# GPS_track2.net
KiCad netlist of a schematic drawn in Altium Designer
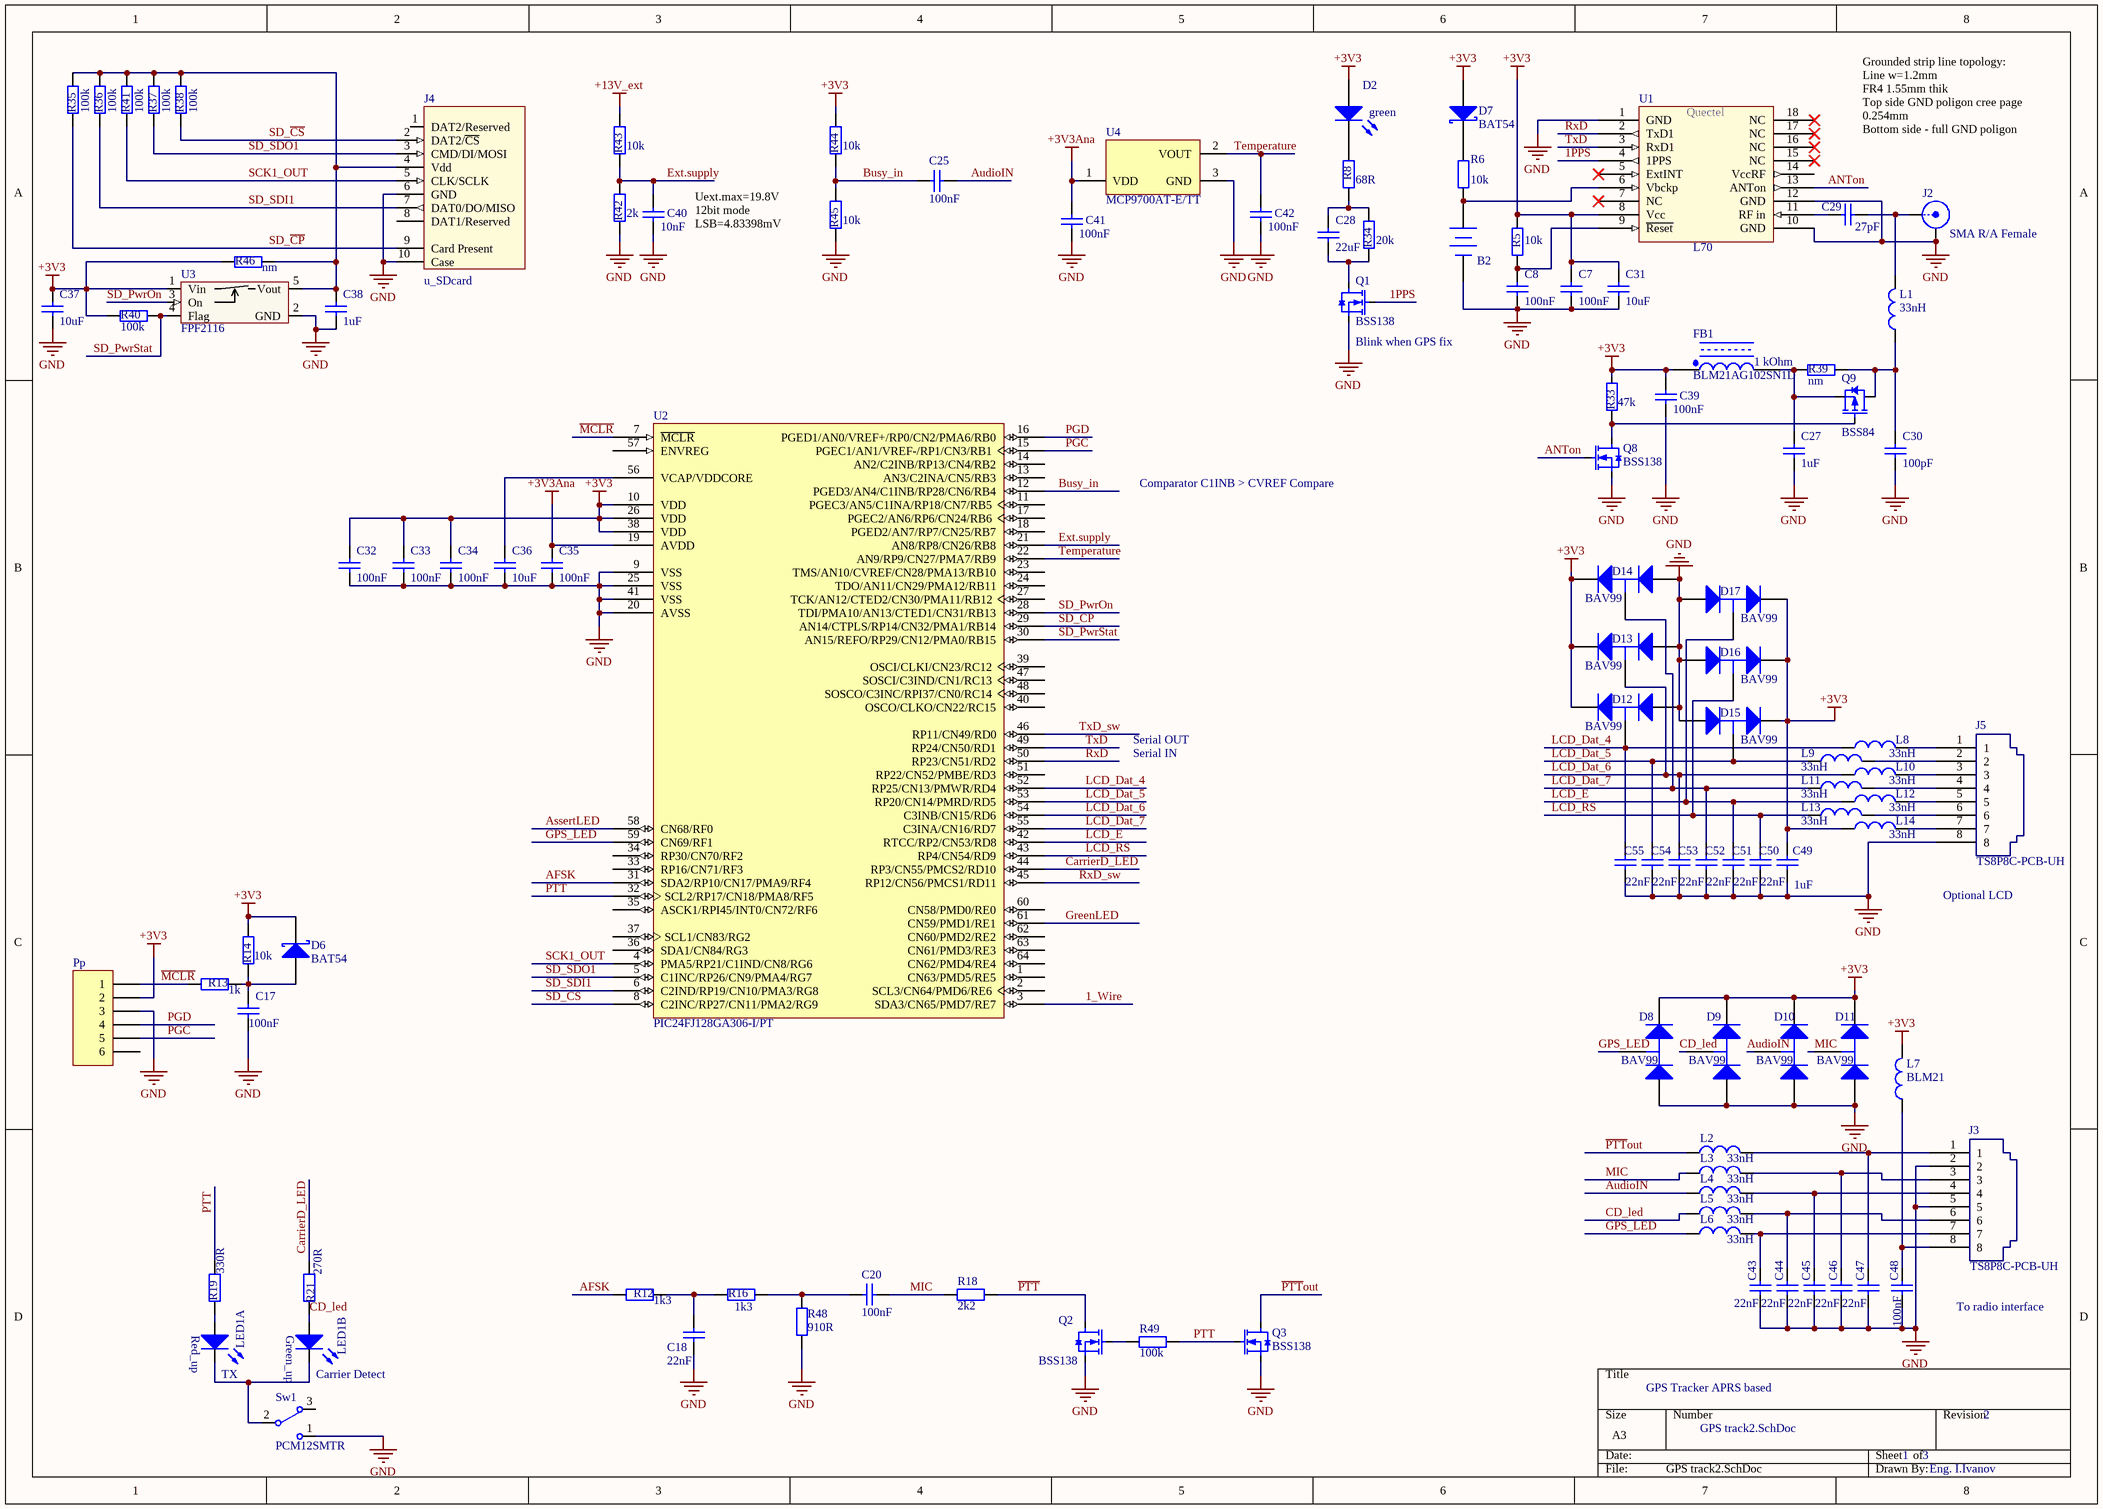
[diagram p0: GPS track2.SchDoc]

(export (version "E")
  (design (tool "Eeschema 10.0.6"))
  (components
    (comp (ref "B2")
      (value "CR2032 holder")
      (footprint "1065 Keystone")
      (fields (field (name "CREATED BY") "Charge"))
      (libsource (lib "ANG_6VA transformers") (part "CR2032_holder"))
    )
    (comp (ref "C7")
      (value "100nF")
      (footprint "2012[0805]")
      (description "Capacitor (Semiconductor SIM Model)")
      (fields (field (name "Comment") "Cap Semi") (field (name "PUBLISHER") "Altium Limited"))
      (libsource (lib "Miscellaneous Devices") (part "Cap Semi"))
    )
    (comp (ref "C8")
      (value "100nF")
      (footprint "2012[0805]")
      (fields (field (name "Comment") "Cap Semi") (field (name "PUBLISHER") "Altium Limited"))
      (libsource (lib "altium-import") (part "root_1__Miscellaneous Devices.IntLib"))
    )
    (comp (ref "C17")
      (value "100nF")
      (footprint "2012[0805]")
      (description "Capacitor (Semiconductor SIM Model)")
      (fields (field (name "Comment") "Cap Semi") (field (name "PUBLISHER") "Altium Limited"))
      (libsource (lib "Miscellaneous Devices") (part "Cap Semi"))
    )
    (comp (ref "C18")
      (value "22nF")
      (footprint "2012[0805]")
      (description "Capacitor (Semiconductor SIM Model)")
      (fields (field (name "Comment") "Cap Semi") (field (name "PUBLISHER") "Altium Limited"))
      (libsource (lib "Miscellaneous Devices") (part "Cap Semi"))
    )
    (comp (ref "C20")
      (value "100nF")
      (footprint "2012[0805]")
      (description "Capacitor (Semiconductor SIM Model)")
      (fields (field (name "Comment") "Cap Semi") (field (name "PUBLISHER") "Altium Limited"))
      (libsource (lib "Miscellaneous Devices") (part "Cap Semi"))
    )
    (comp (ref "C25")
      (value "100nF")
      (footprint "C0805")
      (description "Capacitor (Semiconductor SIM Model)")
      (fields (field (name "Comment") "Cap Semi") (field (name "PUBLISHER") "Altium Limited"))
      (libsource (lib "Miscellaneous Devices") (part "Cap Semi"))
    )
    (comp (ref "C27")
      (value "1uF")
      (footprint "C0805")
      (description "Capacitor (Semiconductor SIM Model)")
      (fields (field (name "Comment") "Cap Semi") (field (name "PUBLISHER") "Altium Limited"))
      (libsource (lib "Miscellaneous Devices") (part "Cap Semi"))
    )
    (comp (ref "C28")
      (value "22uF")
      (footprint "C0805")
      (description "Capacitor (Semiconductor SIM Model)")
      (fields (field (name "Comment") "Cap Semi") (field (name "PUBLISHER") "Altium Limited"))
      (libsource (lib "Miscellaneous Devices") (part "Cap Semi"))
    )
    (comp (ref "C29")
      (value "27pF")
      (footprint "C0805")
      (description "Capacitor (Semiconductor SIM Model)")
      (fields (field (name "Comment") "Cap Semi") (field (name "PUBLISHER") "Altium Limited"))
      (libsource (lib "Miscellaneous Devices") (part "Cap Semi"))
    )
    (comp (ref "C30")
      (value "100pF")
      (footprint "C0805")
      (description "Capacitor (Semiconductor SIM Model)")
      (fields (field (name "Comment") "Cap Semi") (field (name "PUBLISHER") "Altium Limited"))
      (libsource (lib "Miscellaneous Devices") (part "Cap Semi"))
    )
    (comp (ref "C31")
      (value "10uF")
      (footprint "C0805")
      (description "Capacitor (Semiconductor SIM Model)")
      (fields (field (name "Comment") "Cap Semi") (field (name "PUBLISHER") "Altium Limited"))
      (libsource (lib "Miscellaneous Devices") (part "Cap Semi"))
    )
    (comp (ref "C32")
      (value "100nF")
      (footprint "2012[0805]")
      (description "Capacitor (Semiconductor SIM Model)")
      (fields (field (name "Comment") "Cap Semi") (field (name "PUBLISHER") "Altium Limited"))
      (libsource (lib "Miscellaneous Devices") (part "Cap Semi"))
    )
    (comp (ref "C33")
      (value "100nF")
      (footprint "2012[0805]")
      (description "Capacitor (Semiconductor SIM Model)")
      (fields (field (name "Comment") "Cap Semi") (field (name "PUBLISHER") "Altium Limited"))
      (libsource (lib "Miscellaneous Devices") (part "Cap Semi"))
    )
    (comp (ref "C34")
      (value "100nF")
      (footprint "2012[0805]")
      (description "Capacitor (Semiconductor SIM Model)")
      (fields (field (name "Comment") "Cap Semi") (field (name "PUBLISHER") "Altium Limited"))
      (libsource (lib "Miscellaneous Devices") (part "Cap Semi"))
    )
    (comp (ref "C35")
      (value "100nF")
      (footprint "2012[0805]")
      (description "Capacitor (Semiconductor SIM Model)")
      (fields (field (name "PUBLISHER") "Altium Limited"))
      (libsource (lib "Miscellaneous Devices") (part "Cap Semi"))
    )
    (comp (ref "C36")
      (value "10uF")
      (footprint "2012[0805]")
      (description "Capacitor (Semiconductor SIM Model)")
      (fields (field (name "Comment") "Cap Semi") (field (name "PUBLISHER") "Altium Limited"))
      (libsource (lib "Miscellaneous Devices") (part "Cap Semi"))
    )
    (comp (ref "C37")
      (value "10uF")
      (footprint "2012[0805]")
      (description "Capacitor (Semiconductor SIM Model)")
      (fields (field (name "Comment") "Cap Semi") (field (name "PUBLISHER") "Altium Limited"))
      (libsource (lib "Miscellaneous Devices") (part "Cap Semi"))
    )
    (comp (ref "C38")
      (value "1uF")
      (footprint "2012[0805]")
      (description "Capacitor (Semiconductor SIM Model)")
      (fields (field (name "Comment") "Cap Semi") (field (name "PUBLISHER") "Altium Limited"))
      (libsource (lib "Miscellaneous Devices") (part "Cap Semi"))
    )
    (comp (ref "C39")
      (value "100nF")
      (footprint "C0805")
      (description "Capacitor (Semiconductor SIM Model)")
      (fields (field (name "Comment") "Cap Semi") (field (name "PUBLISHER") "Altium Limited"))
      (libsource (lib "Miscellaneous Devices") (part "Cap Semi"))
    )
    (comp (ref "C40")
      (value "10nF")
      (footprint "C0805")
      (description "Capacitor (Semiconductor SIM Model)")
      (fields (field (name "Comment") "Cap Semi") (field (name "PUBLISHER") "Altium Limited"))
      (libsource (lib "Miscellaneous Devices") (part "Cap Semi"))
    )
    (comp (ref "C41")
      (value "100nF")
      (footprint "C0805")
      (description "Capacitor (Semiconductor SIM Model)")
      (fields (field (name "Comment") "Cap Semi") (field (name "PUBLISHER") "Altium Limited"))
      (libsource (lib "Miscellaneous Devices") (part "Cap Semi"))
    )
    (comp (ref "C42")
      (value "100nF")
      (footprint "C0805")
      (description "Capacitor (Semiconductor SIM Model)")
      (fields (field (name "Comment") "Cap Semi") (field (name "PUBLISHER") "Altium Limited"))
      (libsource (lib "Miscellaneous Devices") (part "Cap Semi"))
    )
    (comp (ref "C43")
      (value "22nF")
      (footprint "C0805")
      (description "Capacitor (Semiconductor SIM Model)")
      (fields (field (name "Comment") "Cap Semi") (field (name "PUBLISHER") "Altium Limited"))
      (libsource (lib "Miscellaneous Devices") (part "Cap Semi"))
    )
    (comp (ref "C44")
      (value "22nF")
      (footprint "C0805")
      (description "Capacitor (Semiconductor SIM Model)")
      (fields (field (name "Comment") "Cap Semi") (field (name "PUBLISHER") "Altium Limited"))
      (libsource (lib "Miscellaneous Devices") (part "Cap Semi"))
    )
    (comp (ref "C45")
      (value "22nF")
      (footprint "C0805")
      (description "Capacitor (Semiconductor SIM Model)")
      (fields (field (name "Comment") "Cap Semi") (field (name "PUBLISHER") "Altium Limited"))
      (libsource (lib "Miscellaneous Devices") (part "Cap Semi"))
    )
    (comp (ref "C46")
      (value "22nF")
      (footprint "C0805")
      (description "Capacitor (Semiconductor SIM Model)")
      (fields (field (name "Comment") "Cap Semi") (field (name "PUBLISHER") "Altium Limited"))
      (libsource (lib "Miscellaneous Devices") (part "Cap Semi"))
    )
    (comp (ref "C47")
      (value "22nF")
      (footprint "C0805")
      (description "Capacitor (Semiconductor SIM Model)")
      (fields (field (name "Comment") "Cap Semi") (field (name "PUBLISHER") "Altium Limited"))
      (libsource (lib "Miscellaneous Devices") (part "Cap Semi"))
    )
    (comp (ref "C48")
      (value "100nF")
      (footprint "C0805")
      (description "Capacitor (Semiconductor SIM Model)")
      (fields (field (name "Comment") "Cap Semi") (field (name "PUBLISHER") "Altium Limited"))
      (libsource (lib "Miscellaneous Devices") (part "Cap Semi"))
    )
    (comp (ref "C49")
      (value "1uF")
      (footprint "C0805")
      (description "Capacitor (Semiconductor SIM Model)")
      (fields (field (name "Comment") "Cap Semi") (field (name "PUBLISHER") "Altium Limited"))
      (libsource (lib "Miscellaneous Devices") (part "Cap Semi"))
    )
    (comp (ref "C50")
      (value "22nF")
      (footprint "C0805")
      (description "Capacitor (Semiconductor SIM Model)")
      (fields (field (name "Comment") "Cap Semi") (field (name "PUBLISHER") "Altium Limited"))
      (libsource (lib "Miscellaneous Devices") (part "Cap Semi"))
    )
    (comp (ref "C51")
      (value "22nF")
      (footprint "C0805")
      (description "Capacitor (Semiconductor SIM Model)")
      (fields (field (name "Comment") "Cap Semi") (field (name "PUBLISHER") "Altium Limited"))
      (libsource (lib "Miscellaneous Devices") (part "Cap Semi"))
    )
    (comp (ref "C52")
      (value "22nF")
      (footprint "C0805")
      (description "Capacitor (Semiconductor SIM Model)")
      (fields (field (name "Comment") "Cap Semi") (field (name "PUBLISHER") "Altium Limited"))
      (libsource (lib "Miscellaneous Devices") (part "Cap Semi"))
    )
    (comp (ref "C53")
      (value "22nF")
      (footprint "C0805")
      (description "Capacitor (Semiconductor SIM Model)")
      (fields (field (name "Comment") "Cap Semi") (field (name "PUBLISHER") "Altium Limited"))
      (libsource (lib "Miscellaneous Devices") (part "Cap Semi"))
    )
    (comp (ref "C54")
      (value "22nF")
      (footprint "C0805")
      (description "Capacitor (Semiconductor SIM Model)")
      (fields (field (name "Comment") "Cap Semi") (field (name "PUBLISHER") "Altium Limited"))
      (libsource (lib "Miscellaneous Devices") (part "Cap Semi"))
    )
    (comp (ref "C55")
      (value "22nF")
      (footprint "C0805")
      (description "Capacitor (Semiconductor SIM Model)")
      (fields (field (name "Comment") "Cap Semi") (field (name "PUBLISHER") "Altium Limited"))
      (libsource (lib "Miscellaneous Devices") (part "Cap Semi"))
    )
    (comp (ref "D2")
      (value "OSTG1206C1A")
      (footprint "3.2X1.6X1.1")
      (description "High Performance SMT Chip LED, Green")
      (fields (field (name "PUBLISHER") "Altium Limited"))
      (libsource (lib "Agilent Optoelectronic LED") (part "HSMM-C150"))
    )
    (comp (ref "D6")
      (value "BAT54")
      (footprint "SOT23_N")
      (description "Schottky Barrier Diode")
      (fields (field (name "PUBLISHER") "Altium Limited"))
      (libsource (lib "Philips Discrete Diode - Schottky") (part "BAT54"))
    )
    (comp (ref "D7")
      (value "BAT54")
      (footprint "SOT23_N")
      (description "Schottky Barrier Diode")
      (fields (field (name "PUBLISHER") "Altium Limited"))
      (libsource (lib "Philips Discrete Diode - Schottky") (part "BAT54"))
    )
    (comp (ref "D8")
      (value "BAV99")
      (footprint "SOT-23")
      (description "Silicon Switching Diode Array for High-Speed Switching")
      (fields (field (name "PUBLISHER") "Altium Limited"))
      (libsource (lib "Infineon Discrete Diode") (part "BAV99"))
    )
    (comp (ref "D9")
      (value "BAV99")
      (footprint "SOT-23")
      (description "Silicon Switching Diode Array for High-Speed Switching")
      (fields (field (name "PUBLISHER") "Altium Limited"))
      (libsource (lib "Infineon Discrete Diode") (part "BAV99"))
    )
    (comp (ref "D10")
      (value "BAV99")
      (footprint "SOT-23")
      (description "Silicon Switching Diode Array for High-Speed Switching")
      (fields (field (name "PUBLISHER") "Altium Limited"))
      (libsource (lib "Infineon Discrete Diode") (part "BAV99"))
    )
    (comp (ref "D11")
      (value "BAV99")
      (footprint "SOT-23")
      (description "Silicon Switching Diode Array for High-Speed Switching")
      (fields (field (name "PUBLISHER") "Altium Limited"))
      (libsource (lib "Infineon Discrete Diode") (part "BAV99"))
    )
    (comp (ref "D12")
      (value "BAV99")
      (footprint "SOT-23")
      (description "Silicon Switching Diode Array for High-Speed Switching")
      (fields (field (name "PUBLISHER") "Altium Limited"))
      (libsource (lib "Infineon Discrete Diode") (part "BAV99"))
    )
    (comp (ref "D13")
      (value "BAV99")
      (footprint "SOT-23")
      (description "Silicon Switching Diode Array for High-Speed Switching")
      (fields (field (name "PUBLISHER") "Altium Limited"))
      (libsource (lib "Infineon Discrete Diode") (part "BAV99"))
    )
    (comp (ref "D14")
      (value "BAV99")
      (footprint "SOT-23")
      (description "Silicon Switching Diode Array for High-Speed Switching")
      (fields (field (name "PUBLISHER") "Altium Limited"))
      (libsource (lib "Infineon Discrete Diode") (part "BAV99"))
    )
    (comp (ref "D15")
      (value "BAV99")
      (footprint "SOT-23")
      (description "Silicon Switching Diode Array for High-Speed Switching")
      (fields (field (name "PUBLISHER") "Altium Limited"))
      (libsource (lib "Infineon Discrete Diode") (part "BAV99"))
    )
    (comp (ref "D16")
      (value "BAV99")
      (footprint "SOT-23")
      (description "Silicon Switching Diode Array for High-Speed Switching")
      (fields (field (name "PUBLISHER") "Altium Limited"))
      (libsource (lib "Infineon Discrete Diode") (part "BAV99"))
    )
    (comp (ref "D17")
      (value "BAV99")
      (footprint "SOT-23")
      (description "Silicon Switching Diode Array for High-Speed Switching")
      (fields (field (name "PUBLISHER") "Altium Limited"))
      (libsource (lib "Infineon Discrete Diode") (part "BAV99"))
    )
    (comp (ref "FB1")
      (value "BLM21AG102SN1D")
      (footprint "RESC2012N")
      (description "Isolated Inductor")
      (fields (field (name "ALTIUM_VALUE") "1 kOhm") (field (name "PUBLISHER") "Altium Limited"))
      (libsource (lib "Miscellaneous Devices") (part "Inductor Isolated"))
    )
    (comp (ref "J2")
      (value "SMA R/A Female")
      (footprint "SMA R/A PCB")
      (fields (field (name "Comment") "SMA R/A PCB") (field (name "CREATED BY") "Charge"))
      (libsource (lib "*") (part "SMA R/A PCB"))
    )
    (comp (ref "J3")
      (value "TS8P8C-PCB-UH")
      (footprint "TS8P8C-PCB-UH")
      (description "Cvilux - CJ3188A1100")
      (libsource (lib "ANG_6VA transformers") (part "TS8P8C-PCB-UH"))
    )
    (comp (ref "J4")
      (value "u_SDcard")
      (footprint "112A-TAAR-R02")
      (fields (field (name "MANUFACTURER") "Attend Technology") (field (name "Comment") "microSD Socket"))
      (libsource (lib "ANG_6VA transformers") (part "Micro SD Socket PP T1"))
    )
    (comp (ref "J5")
      (value "TS8P8C-PCB-UH")
      (footprint "TS8P8C-PCB-UH")
      (description "Cvilux - CJ3188A1100")
      (libsource (lib "ANG_6VA transformers") (part "TS8P8C-PCB-UH"))
    )
    (comp (ref "L1")
      (value "33nH")
      (footprint "CCFH0805 C Series")
      (fields (field (name "Comment") "CCFH 0805 series choke"))
      (libsource (lib "ANG_6VA transformers") (part "CCFH0805 coil Coils"))
    )
    (comp (ref "L2")
      (value "33nH")
      (footprint "CCFH0805 C Series")
      (fields (field (name "Comment") "CCFH 0805 series choke"))
      (libsource (lib "ANG_6VA transformers") (part "CCFH0805 coil Coils"))
    )
    (comp (ref "L3")
      (value "33nH")
      (footprint "CCFH0805 C Series")
      (fields (field (name "Comment") "CCFH 0805 series choke"))
      (libsource (lib "ANG_6VA transformers") (part "CCFH0805 coil Coils"))
    )
    (comp (ref "L4")
      (value "33nH")
      (footprint "CCFH0805 C Series")
      (fields (field (name "Comment") "CCFH 0805 series choke"))
      (libsource (lib "ANG_6VA transformers") (part "CCFH0805 coil Coils"))
    )
    (comp (ref "L5")
      (value "33nH")
      (footprint "CCFH0805 C Series")
      (fields (field (name "Comment") "CCFH 0805 series choke"))
      (libsource (lib "ANG_6VA transformers") (part "CCFH0805 coil Coils"))
    )
    (comp (ref "L6")
      (value "33nH")
      (footprint "CCFH0805 C Series")
      (fields (field (name "Comment") "CCFH 0805 series choke"))
      (libsource (lib "ANG_6VA transformers") (part "CCFH0805 coil Coils"))
    )
    (comp (ref "L7")
      (value "BLM21")
      (footprint "CCFH0805 C Series")
      (fields (field (name "Comment") "CCFH 0805 series choke"))
      (libsource (lib "ANG_6VA transformers") (part "CCFH0805 coil Coils"))
    )
    (comp (ref "L8")
      (value "33nH")
      (footprint "CCFH0805 C Series")
      (fields (field (name "Comment") "CCFH 0805 series choke"))
      (libsource (lib "ANG_6VA transformers") (part "CCFH0805 coil Coils"))
    )
    (comp (ref "L9")
      (value "33nH")
      (footprint "CCFH0805 C Series")
      (fields (field (name "Comment") "CCFH 0805 series choke"))
      (libsource (lib "ANG_6VA transformers") (part "CCFH0805 coil Coils"))
    )
    (comp (ref "L10")
      (value "33nH")
      (footprint "CCFH0805 C Series")
      (fields (field (name "Comment") "CCFH 0805 series choke"))
      (libsource (lib "ANG_6VA transformers") (part "CCFH0805 coil Coils"))
    )
    (comp (ref "L11")
      (value "33nH")
      (footprint "CCFH0805 C Series")
      (fields (field (name "Comment") "CCFH 0805 series choke"))
      (libsource (lib "ANG_6VA transformers") (part "CCFH0805 coil Coils"))
    )
    (comp (ref "L12")
      (value "33nH")
      (footprint "CCFH0805 C Series")
      (fields (field (name "Comment") "CCFH 0805 series choke"))
      (libsource (lib "ANG_6VA transformers") (part "CCFH0805 coil Coils"))
    )
    (comp (ref "L13")
      (value "33nH")
      (footprint "CCFH0805 C Series")
      (fields (field (name "Comment") "CCFH 0805 series choke"))
      (libsource (lib "ANG_6VA transformers") (part "CCFH0805 coil Coils"))
    )
    (comp (ref "L14")
      (value "33nH")
      (footprint "CCFH0805 C Series")
      (fields (field (name "Comment") "CCFH 0805 series choke"))
      (libsource (lib "ANG_6VA transformers") (part "CCFH0805 coil Coils"))
    )
    (comp (ref "LED1")
      (value "4x LED's")
      (footprint "515-1061F_2x dual LED's")
      (libsource (lib "ANG_6VA transformers") (part "515-1061F_2x dual LED's"))
    )
    (comp (ref "Pp")
      (value "Header 6")
      (footprint "HDR1X6")
      (description "Header, 6-Pin")
      (fields (field (name "PUBLISHER") "Altium Limited"))
      (libsource (lib "Miscellaneous Connectors") (part "Header 6"))
    )
    (comp (ref "Q1")
      (value "BSS138")
      (footprint "SOT-23_my")
      (fields (field (name "Comment") "My BSS138"))
      (libsource (lib "ANG_6VA transformers") (part "BSS138_my"))
    )
    (comp (ref "Q2")
      (value "BSS138")
      (footprint "SOT-23_my")
      (fields (field (name "Comment") "My BSS138"))
      (libsource (lib "ANG_6VA transformers") (part "BSS138_my"))
    )
    (comp (ref "Q3")
      (value "BSS138")
      (footprint "SOT-23_my")
      (fields (field (name "Comment") "My BSS138"))
      (libsource (lib "ANG_6VA transformers") (part "BSS138_my"))
    )
    (comp (ref "Q8")
      (value "BSS138")
      (footprint "SOT-23_my")
      (fields (field (name "Comment") "My BSS138"))
      (libsource (lib "ANG_6VA transformers") (part "BSS138_my"))
    )
    (comp (ref "Q9")
      (value "BSS84")
      (footprint "SOT-23_my")
      (fields (field (name "MANUFACTURER") "Zetex; Rohm, etc") (field (name "Comment") "My SOT23 BSS84"))
      (libsource (lib "ANG_6VA transformers") (part "BSS84_my"))
    )
    (comp (ref "R5")
      (value "10k")
      (footprint "2012[0805]")
      (description "Resistor")
      (fields (field (name "Comment") "Res2") (field (name "PUBLISHER") "Altium Limited"))
      (libsource (lib "") (part "Res2_1"))
    )
    (comp (ref "R6")
      (value "10k")
      (footprint "2012[0805]")
      (description "Resistor")
      (fields (field (name "Comment") "Res2") (field (name "PUBLISHER") "Altium Limited"))
      (libsource (lib "") (part "Res2_1"))
    )
    (comp (ref "R8")
      (value "68R")
      (footprint "2012[0805]")
      (description "Resistor")
      (fields (field (name "Comment") "Res2") (field (name "PUBLISHER") "Altium Limited"))
      (libsource (lib "") (part "Res2_1"))
    )
    (comp (ref "R12")
      (value "1k3")
      (footprint "RESC2012N")
      (description "Resistor")
      (fields (field (name "Comment") "Res2") (field (name "PUBLISHER") "Altium Limited"))
      (libsource (lib "") (part "Res2_2"))
    )
    (comp (ref "R13")
      (value "1k")
      (footprint "RESC2012N")
      (description "Resistor")
      (fields (field (name "Comment") "Res2") (field (name "PUBLISHER") "Altium Limited"))
      (libsource (lib "") (part "Res2_2"))
    )
    (comp (ref "R14")
      (value "10k")
      (footprint "2012[0805]")
      (description "Resistor")
      (fields (field (name "Comment") "Res2") (field (name "PUBLISHER") "Altium Limited"))
      (libsource (lib "Miscellaneous Devices") (part "Res2"))
    )
    (comp (ref "R16")
      (value "1k3")
      (footprint "RESC2012N")
      (description "Resistor")
      (fields (field (name "Comment") "Res2") (field (name "PUBLISHER") "Altium Limited"))
      (libsource (lib "") (part "Res2_2"))
    )
    (comp (ref "R18")
      (value "2k2")
      (footprint "2012[0805]")
      (description "Resistor")
      (fields (field (name "Comment") "Res2") (field (name "PUBLISHER") "Altium Limited"))
      (libsource (lib "") (part "Res2_2"))
    )
    (comp (ref "R19")
      (value "330R")
      (footprint "2012[0805]")
      (description "Resistor")
      (fields (field (name "Comment") "Res2") (field (name "PUBLISHER") "Altium Limited"))
      (libsource (lib "Miscellaneous Devices") (part "Res2"))
    )
    (comp (ref "R21")
      (value "270R")
      (footprint "2012[0805]")
      (description "Resistor")
      (fields (field (name "Comment") "Res2") (field (name "PUBLISHER") "Altium Limited"))
      (libsource (lib "Miscellaneous Devices") (part "Res2"))
    )
    (comp (ref "R33")
      (value "47k")
      (footprint "2012[0805]")
      (description "Resistor")
      (fields (field (name "Comment") "Res2") (field (name "PUBLISHER") "Altium Limited"))
      (libsource (lib "Miscellaneous Devices") (part "Res2"))
    )
    (comp (ref "R34")
      (value "20k")
      (footprint "2012[0805]")
      (description "Resistor")
      (fields (field (name "Comment") "Res2") (field (name "PUBLISHER") "Altium Limited"))
      (libsource (lib "Miscellaneous Devices") (part "Res2"))
    )
    (comp (ref "R35")
      (value "100k")
      (footprint "2012[0805]")
      (description "Resistor")
      (fields (field (name "Comment") "Res2") (field (name "PUBLISHER") "Altium Limited"))
      (libsource (lib "Miscellaneous Devices") (part "Res2"))
    )
    (comp (ref "R36")
      (value "100k")
      (footprint "2012[0805]")
      (description "Resistor")
      (fields (field (name "Comment") "Res2") (field (name "PUBLISHER") "Altium Limited"))
      (libsource (lib "Miscellaneous Devices") (part "Res2"))
    )
    (comp (ref "R37")
      (value "100k")
      (footprint "2012[0805]")
      (description "Resistor")
      (fields (field (name "Comment") "Res2") (field (name "PUBLISHER") "Altium Limited"))
      (libsource (lib "Miscellaneous Devices") (part "Res2"))
    )
    (comp (ref "R38")
      (value "100k")
      (footprint "2012[0805]")
      (description "Resistor")
      (fields (field (name "Comment") "Res2") (field (name "PUBLISHER") "Altium Limited"))
      (libsource (lib "Miscellaneous Devices") (part "Res2"))
    )
    (comp (ref "R39")
      (value "nm")
      (footprint "2012[0805]")
      (description "Resistor")
      (fields (field (name "Comment") "Res2") (field (name "PUBLISHER") "Altium Limited"))
      (libsource (lib "") (part "Res2_3"))
    )
    (comp (ref "R40")
      (value "100k")
      (footprint "2012[0805]")
      (description "Resistor")
      (fields (field (name "Comment") "Res2") (field (name "PUBLISHER") "Altium Limited"))
      (libsource (lib "") (part "Res2_3"))
    )
    (comp (ref "R41")
      (value "100k")
      (footprint "2012[0805]")
      (description "Resistor")
      (fields (field (name "Comment") "Res2") (field (name "PUBLISHER") "Altium Limited"))
      (libsource (lib "") (part "Res2_1"))
    )
    (comp (ref "R42")
      (value "2k")
      (footprint "2012[0805]")
      (description "Resistor")
      (fields (field (name "Comment") "Res2") (field (name "PUBLISHER") "Altium Limited"))
      (libsource (lib "Miscellaneous Devices") (part "Res2"))
    )
    (comp (ref "R43")
      (value "10k")
      (footprint "2012[0805]")
      (description "Resistor")
      (fields (field (name "Comment") "Res2") (field (name "PUBLISHER") "Altium Limited"))
      (libsource (lib "Miscellaneous Devices") (part "Res2"))
    )
    (comp (ref "R44")
      (value "10k")
      (footprint "2012[0805]")
      (description "Resistor")
      (fields (field (name "Comment") "Res2") (field (name "PUBLISHER") "Altium Limited"))
      (libsource (lib "Miscellaneous Devices") (part "Res2"))
    )
    (comp (ref "R45")
      (value "10k")
      (footprint "2012[0805]")
      (description "Resistor")
      (fields (field (name "Comment") "Res2") (field (name "PUBLISHER") "Altium Limited"))
      (libsource (lib "Miscellaneous Devices") (part "Res2"))
    )
    (comp (ref "R46")
      (value "nm")
      (footprint "2012[0805]")
      (description "Resistor")
      (fields (field (name "Comment") "Res2") (field (name "PUBLISHER") "Altium Limited"))
      (libsource (lib "") (part "Res2_3"))
    )
    (comp (ref "R48")
      (value "910R")
      (footprint "2012[0805]")
      (description "Resistor")
      (fields (field (name "Comment") "Res2") (field (name "PUBLISHER") "Altium Limited"))
      (libsource (lib "") (part "Res2_1"))
    )
    (comp (ref "R49")
      (value "100k")
      (footprint "2012[0805]")
      (description "Resistor")
      (fields (field (name "Comment") "Res2") (field (name "PUBLISHER") "Altium Limited"))
      (libsource (lib "") (part "Res2_1"))
    )
    (comp (ref "Sw1")
      (value "PCM12SMTR")
      (footprint "PCM12SMTR")
      (description "Ultraminiature Surface Mount Slide Switch")
      (fields (field (name "MANUFACTURER") "C & K COMPONENTS") (field (name "Comment") "SPDT"))
      (libsource (lib "ANG_6VA transformers") (part "PCM12SMTR"))
    )
    (comp (ref "U1")
      (value "L70")
      (footprint "L70")
      (fields (field (name "MANUFACTURER") "Quectel") (field (name "Comment") "L70 Quectel"))
      (libsource (lib "ANG_6VA transformers") (part "L70 Quectel"))
    )
    (comp (ref "U2")
      (value "PIC24FJ128GA306-I/PT")
      (footprint "TQFP-PT64_N")
      (fields (field (name "PUBLISHER") "Altium Limited"))
      (libsource (lib "Microchip Microcontroller 16-Bit PIC24F") (part "PIC24FJ128GA106-I/PT"))
    )
    (comp (ref "U3")
      (value "FPF2116")
      (footprint "SOT23-5AN")
      (description "IntelliMAX™ Advanced Load Management Switch")
      (fields (field (name "MANUFACTURER") "Fairchild Semiconductor"))
      (libsource (lib "ANG_6VA transformers") (part "FPF2116"))
    )
    (comp (ref "U4")
      (value "MCP9700AT-E/TT")
      (footprint "SOT-23-TT3_N")
      (description "Low-Power Linear Active Thermistor IC, 3-Pin SOT-23, Extended Temperature, Tape and Reel")
      (fields (field (name "PUBLISHER") "Altium Limited"))
      (libsource (lib "Microchip Thermal Management") (part "MCP9700AT-E/TT"))
    )
  )
  (nets
    (net (code "1") (name "+3V3") (class "Default")
      (node (ref "C31") (pin "1") (pinfunction "1_1") (pintype "passive"))
      (node (ref "C32") (pin "2") (pinfunction "2_2") (pintype "passive"))
      (node (ref "C33") (pin "2") (pinfunction "2_2") (pintype "passive"))
      (node (ref "C34") (pin "2") (pinfunction "2_2") (pintype "passive"))
      (node (ref "C37") (pin "2") (pinfunction "2_2") (pintype "passive"))
      (node (ref "C39") (pin "1") (pinfunction "1_1") (pintype "passive"))
      (node (ref "C49") (pin "1") (pinfunction "1_1") (pintype "passive"))
      (node (ref "C7") (pin "2") (pinfunction "2_2") (pintype "passive"))
      (node (ref "D10") (pin "2") (pinfunction "K_2") (pintype "passive"))
      (node (ref "D11") (pin "2") (pinfunction "K_2") (pintype "passive"))
      (node (ref "D12") (pin "2") (pinfunction "K_2") (pintype "passive"))
      (node (ref "D13") (pin "2") (pinfunction "K_2") (pintype "passive"))
      (node (ref "D14") (pin "2") (pinfunction "K_2") (pintype "passive"))
      (node (ref "D15") (pin "2") (pinfunction "K_2") (pintype "passive"))
      (node (ref "D16") (pin "2") (pinfunction "K_2") (pintype "passive"))
      (node (ref "D17") (pin "2") (pinfunction "K_2") (pintype "passive"))
      (node (ref "D2") (pin "1") (pinfunction "A_1") (pintype "passive"))
      (node (ref "D6") (pin "3") (pinfunction "K_3") (pintype "passive"))
      (node (ref "D7") (pin "1") (pinfunction "A_1") (pintype "passive"))
      (node (ref "D8") (pin "2") (pinfunction "K_2") (pintype "passive"))
      (node (ref "D9") (pin "2") (pinfunction "K_2") (pintype "passive"))
      (node (ref "FB1") (pin "1") (pinfunction "1_1") (pintype "passive"))
      (node (ref "L14") (pin "1") (pinfunction "1_1") (pintype "passive"))
      (node (ref "L7") (pin "2") (pinfunction "2_2") (pintype "passive"))
      (node (ref "Pp") (pin "2") (pinfunction "2_2") (pintype "passive"))
      (node (ref "R14") (pin "1") (pinfunction "1_1") (pintype "passive"))
      (node (ref "R33") (pin "1") (pinfunction "1_1") (pintype "passive"))
      (node (ref "R40") (pin "1") (pinfunction "1_1") (pintype "passive"))
      (node (ref "R44") (pin "1") (pinfunction "1_1") (pintype "passive"))
      (node (ref "R46") (pin "1") (pinfunction "1_1") (pintype "passive"))
      (node (ref "R5") (pin "2") (pinfunction "2_2") (pintype "passive"))
      (node (ref "U1") (pin "8") (pinfunction "Vcc_8") (pintype "power_in"))
      (node (ref "U2") (pin "10") (pinfunction "VDD_10") (pintype "power_in"))
      (node (ref "U2") (pin "26") (pinfunction "VDD_26") (pintype "power_in"))
      (node (ref "U2") (pin "38") (pinfunction "VDD_38") (pintype "power_in"))
      (node (ref "U3") (pin "1") (pinfunction "Vin_1") (pintype "power_in"))
    )
    (net (code "2") (name "+3V3Ana") (class "Default")
      (node (ref "C35") (pin "2") (pinfunction "2_2") (pintype "passive"))
      (node (ref "C41") (pin "1") (pinfunction "1_1") (pintype "passive"))
      (node (ref "U2") (pin "19") (pinfunction "AVDD_19") (pintype "power_in"))
      (node (ref "U4") (pin "1") (pinfunction "VDD_1") (pintype "power_in"))
    )
    (net (code "3") (name "+13V_ext") (class "Default")
      (node (ref "R43") (pin "1") (pinfunction "1_1") (pintype "passive"))
    )
    (net (code "4") (name "/1PPS") (class "Default")
      (node (ref "Q1") (pin "1") (pinfunction "G_1") (pintype "passive"))
      (node (ref "U1") (pin "4") (pinfunction "1PPS_4") (pintype "output"))
    )
    (net (code "5") (name "/1_Wire") (class "Default")
      (node (ref "U2") (pin "3") (pinfunction "SDA3/CN65/PMD7/RE7_3") (pintype "bidirectional"))
    )
    (net (code "6") (name "/AFSK") (class "Default")
      (node (ref "R12") (pin "2") (pinfunction "2_2") (pintype "passive"))
      (node (ref "U2") (pin "31") (pinfunction "SDA2/RP10/CN17/PMA9/RF4_31") (pintype "bidirectional"))
    )
    (net (code "7") (name "/ANTon") (class "Default")
      (node (ref "Q8") (pin "1") (pinfunction "G_1") (pintype "passive"))
      (node (ref "U1") (pin "13") (pinfunction "ANTon_13") (pintype "output"))
    )
    (net (code "8") (name "/AssertLED") (class "Default")
      (node (ref "U2") (pin "58") (pinfunction "CN68/RF0_58") (pintype "bidirectional"))
    )
    (net (code "9") (name "/AudioIN") (class "Default")
      (node (ref "C25") (pin "2") (pinfunction "2_2") (pintype "passive"))
      (node (ref "D10") (pin "3") (pinfunction "C_3") (pintype "passive"))
      (node (ref "L4") (pin "1") (pinfunction "1_1") (pintype "passive"))
    )
    (net (code "10") (name "/Busy_in") (class "Default")
      (node (ref "C25") (pin "1") (pinfunction "1_1") (pintype "passive"))
      (node (ref "R44") (pin "2") (pinfunction "2_2") (pintype "passive"))
      (node (ref "R45") (pin "1") (pinfunction "1_1") (pintype "passive"))
      (node (ref "U2") (pin "12") (pinfunction "PGED3/AN4/C1INB/RP28/CN6/RB4_12") (pintype "bidirectional"))
    )
    (net (code "11") (name "/CD_led") (class "Default")
      (node (ref "D9") (pin "3") (pinfunction "C_3") (pintype "passive"))
      (node (ref "L5") (pin "1") (pinfunction "1_1") (pintype "passive"))
      (node (ref "LED1") (pin "4u") (pinfunction "A_4u") (pintype "passive"))
      (node (ref "R21") (pin "2") (pinfunction "2_2") (pintype "passive"))
    )
    (net (code "12") (name "/CarrierD_LED") (class "Default")
      (node (ref "R21") (pin "1") (pinfunction "1_1") (pintype "passive"))
      (node (ref "U2") (pin "44") (pinfunction "RP3/CN55/PMCS2/RD10_44") (pintype "bidirectional"))
    )
    (net (code "13") (name "/Ext.supply") (class "Default")
      (node (ref "C40") (pin "1") (pinfunction "1_1") (pintype "passive"))
      (node (ref "R42") (pin "1") (pinfunction "1_1") (pintype "passive"))
      (node (ref "R43") (pin "2") (pinfunction "2_2") (pintype "passive"))
      (node (ref "U2") (pin "21") (pinfunction "AN8/RP8/CN26/RB8_21") (pintype "bidirectional"))
    )
    (net (code "14") (name "/GPS_LED") (class "Default")
      (node (ref "D8") (pin "3") (pinfunction "C_3") (pintype "passive"))
      (node (ref "L6") (pin "1") (pinfunction "1_1") (pintype "passive"))
      (node (ref "U2") (pin "59") (pinfunction "CN69/RF1_59") (pintype "bidirectional"))
    )
    (net (code "15") (name "/GreenLED") (class "Default")
      (node (ref "U2") (pin "61") (pinfunction "CN59/PMD1/RE1_61") (pintype "bidirectional"))
    )
    (net (code "16") (name "/LCD_Dat_4") (class "Default")
      (node (ref "C55") (pin "1") (pinfunction "1_1") (pintype "passive"))
      (node (ref "D12") (pin "3") (pinfunction "C_3") (pintype "passive"))
      (node (ref "L8") (pin "1") (pinfunction "1_1") (pintype "passive"))
      (node (ref "U2") (pin "52") (pinfunction "RP25/CN13/PMWR/RD4_52") (pintype "bidirectional"))
    )
    (net (code "17") (name "/LCD_Dat_5") (class "Default")
      (node (ref "C54") (pin "1") (pinfunction "1_1") (pintype "passive"))
      (node (ref "D15") (pin "3") (pinfunction "C_3") (pintype "passive"))
      (node (ref "L9") (pin "1") (pinfunction "1_1") (pintype "passive"))
      (node (ref "U2") (pin "53") (pinfunction "RP20/CN14/PMRD/RD5_53") (pintype "bidirectional"))
    )
    (net (code "18") (name "/LCD_Dat_6") (class "Default")
      (node (ref "C53") (pin "1") (pinfunction "1_1") (pintype "passive"))
      (node (ref "D13") (pin "3") (pinfunction "C_3") (pintype "passive"))
      (node (ref "L10") (pin "1") (pinfunction "1_1") (pintype "passive"))
      (node (ref "U2") (pin "54") (pinfunction "C3INB/CN15/RD6_54") (pintype "bidirectional"))
    )
    (net (code "19") (name "/LCD_Dat_7") (class "Default")
      (node (ref "C52") (pin "1") (pinfunction "1_1") (pintype "passive"))
      (node (ref "D14") (pin "3") (pinfunction "C_3") (pintype "passive"))
      (node (ref "L11") (pin "1") (pinfunction "1_1") (pintype "passive"))
      (node (ref "U2") (pin "55") (pinfunction "C3INA/CN16/RD7_55") (pintype "bidirectional"))
    )
    (net (code "20") (name "/LCD_E") (class "Default")
      (node (ref "C51") (pin "1") (pinfunction "1_1") (pintype "passive"))
      (node (ref "D17") (pin "3") (pinfunction "C_3") (pintype "passive"))
      (node (ref "L12") (pin "1") (pinfunction "1_1") (pintype "passive"))
      (node (ref "U2") (pin "42") (pinfunction "RTCC/RP2/CN53/RD8_42") (pintype "bidirectional"))
    )
    (net (code "21") (name "/LCD_RS") (class "Default")
      (node (ref "C50") (pin "1") (pinfunction "1_1") (pintype "passive"))
      (node (ref "D16") (pin "3") (pinfunction "C_3") (pintype "passive"))
      (node (ref "L13") (pin "1") (pinfunction "1_1") (pintype "passive"))
      (node (ref "U2") (pin "43") (pinfunction "RP4/CN54/RD9_43") (pintype "bidirectional"))
    )
    (net (code "22") (name "/MIC") (class "Default")
      (node (ref "C20") (pin "1") (pinfunction "1_1") (pintype "passive"))
      (node (ref "D11") (pin "3") (pinfunction "C_3") (pintype "passive"))
      (node (ref "L3") (pin "1") (pinfunction "1_1") (pintype "passive"))
      (node (ref "R18") (pin "2") (pinfunction "2_2") (pintype "passive"))
    )
    (net (code "23") (name "/PGC") (class "Default")
      (node (ref "Pp") (pin "5") (pinfunction "5_5") (pintype "passive"))
      (node (ref "U2") (pin "15") (pinfunction "PGEC1/AN1/VREF-/RP1/CN3/RB1_15") (pintype "bidirectional"))
    )
    (net (code "24") (name "/PGD") (class "Default")
      (node (ref "Pp") (pin "4") (pinfunction "4_4") (pintype "passive"))
      (node (ref "U2") (pin "16") (pinfunction "PGED1/AN0/VREF+/RP0/CN2/PMA6/RB0_16") (pintype "bidirectional"))
    )
    (net (code "25") (name "/PTT") (class "Default")
      (node (ref "Q3") (pin "1") (pinfunction "G_1") (pintype "passive"))
      (node (ref "R19") (pin "1") (pinfunction "1_1") (pintype "passive"))
      (node (ref "R49") (pin "2") (pinfunction "2_2") (pintype "passive"))
      (node (ref "U2") (pin "32") (pinfunction "SCL2/RP17/CN18/PMA8/RF5_32") (pintype "bidirectional"))
    )
    (net (code "26") (name "/RxD") (class "Default")
      (node (ref "U1") (pin "2") (pinfunction "TxD1_2") (pintype "output"))
      (node (ref "U2") (pin "50") (pinfunction "RP23/CN51/RD2_50") (pintype "bidirectional"))
    )
    (net (code "27") (name "/RxD_sw") (class "Default")
      (node (ref "U2") (pin "45") (pinfunction "RP12/CN56/PMCS1/RD11_45") (pintype "bidirectional"))
    )
    (net (code "28") (name "/SCK1_OUT") (class "Default")
      (node (ref "J4") (pin "5") (pinfunction "CLK/SCLK_5") (pintype "input"))
      (node (ref "R41") (pin "1") (pinfunction "1_1") (pintype "passive"))
      (node (ref "U2") (pin "4") (pinfunction "PMA5/RP21/C1IND/CN8/RG6_4") (pintype "bidirectional"))
    )
    (net (code "29") (name "/SD_PwrOn") (class "Default")
      (node (ref "U2") (pin "28") (pinfunction "TDI/PMA10/AN13/CTED1/CN31/RB13_28") (pintype "bidirectional"))
      (node (ref "U3") (pin "3") (pinfunction "On_3") (pintype "input"))
    )
    (net (code "30") (name "/SD_PwrStat") (class "Default")
      (node (ref "R40") (pin "2") (pinfunction "2_2") (pintype "passive"))
      (node (ref "U2") (pin "30") (pinfunction "AN15/REFO/RP29/CN12/PMA0/RB15_30") (pintype "bidirectional"))
      (node (ref "U3") (pin "4") (pinfunction "Flag_4") (pintype "open_collector"))
    )
    (net (code "31") (name "/SD_SDI1") (class "Default")
      (node (ref "J4") (pin "7") (pinfunction "DAT0/DO/MISO_7") (pintype "output"))
      (node (ref "R36") (pin "2") (pinfunction "2_2") (pintype "passive"))
      (node (ref "U2") (pin "6") (pinfunction "C2IND/RP19/CN10/PMA3/RG8_6") (pintype "bidirectional"))
    )
    (net (code "32") (name "/SD_SDO1") (class "Default")
      (node (ref "J4") (pin "3") (pinfunction "CMD/DI/MOSI_3") (pintype "input"))
      (node (ref "R37") (pin "2") (pinfunction "2_2") (pintype "passive"))
      (node (ref "U2") (pin "5") (pinfunction "C1INC/RP26/CN9/PMA4/RG7_5") (pintype "bidirectional"))
    )
    (net (code "33") (name "/SD_~{CP}") (class "Default")
      (node (ref "J4") (pin "9") (pinfunction "Card_Present_9") (pintype "passive"))
      (node (ref "R35") (pin "2") (pinfunction "2_2") (pintype "passive"))
      (node (ref "U2") (pin "29") (pinfunction "AN14/CTPLS/RP14/CN32/PMA1/RB14_29") (pintype "bidirectional"))
    )
    (net (code "34") (name "/SD_~{CS}") (class "Default")
      (node (ref "J4") (pin "2") (pinfunction "DAT2/~{CS}_2") (pintype "input"))
      (node (ref "R38") (pin "2") (pinfunction "2_2") (pintype "passive"))
      (node (ref "U2") (pin "8") (pinfunction "C2INC/RP27/CN11/PMA2/RG9_8") (pintype "bidirectional"))
    )
    (net (code "35") (name "/Temperature") (class "Default")
      (node (ref "C42") (pin "1") (pinfunction "1_1") (pintype "passive"))
      (node (ref "U2") (pin "22") (pinfunction "AN9/RP9/CN27/PMA7/RB9_22") (pintype "bidirectional"))
      (node (ref "U4") (pin "2") (pinfunction "VOUT_2") (pintype "power_in"))
    )
    (net (code "36") (name "/TxD") (class "Default")
      (node (ref "U1") (pin "3") (pinfunction "RxD1_3") (pintype "input"))
      (node (ref "U2") (pin "49") (pinfunction "RP24/CN50/RD1_49") (pintype "bidirectional"))
    )
    (net (code "37") (name "/TxD_sw") (class "Default")
      (node (ref "U2") (pin "46") (pinfunction "RP11/CN49/RD0_46") (pintype "bidirectional"))
    )
    (net (code "38") (name "/~{MCLR}") (class "Default")
      (node (ref "Pp") (pin "1") (pinfunction "1_1") (pintype "passive"))
      (node (ref "R13") (pin "2") (pinfunction "2_2") (pintype "passive"))
      (node (ref "U2") (pin "7") (pinfunction "~{MCLR}_7") (pintype "input"))
    )
    (net (code "39") (name "/~{PTT}") (class "Default")
      (node (ref "Q2") (pin "3") (pinfunction "D_3") (pintype "passive"))
      (node (ref "R18") (pin "1") (pinfunction "1_1") (pintype "passive"))
    )
    (net (code "40") (name "/~{PTT}out") (class "Default")
      (node (ref "L2") (pin "1") (pinfunction "1_1") (pintype "passive"))
      (node (ref "Q3") (pin "3") (pinfunction "D_3") (pintype "passive"))
    )
    (net (code "41") (name "GND") (class "Default")
      (node (ref "B2") (pin "2") (pinfunction "-_2") (pintype "passive"))
      (node (ref "C17") (pin "1") (pinfunction "1_1") (pintype "passive"))
      (node (ref "C18") (pin "1") (pinfunction "1_1") (pintype "passive"))
      (node (ref "C27") (pin "1") (pinfunction "1_1") (pintype "passive"))
      (node (ref "C30") (pin "2") (pinfunction "2_2") (pintype "passive"))
      (node (ref "C31") (pin "2") (pinfunction "2_2") (pintype "passive"))
      (node (ref "C32") (pin "1") (pinfunction "1_1") (pintype "passive"))
      (node (ref "C33") (pin "1") (pinfunction "1_1") (pintype "passive"))
      (node (ref "C34") (pin "1") (pinfunction "1_1") (pintype "passive"))
      (node (ref "C35") (pin "1") (pinfunction "1_1") (pintype "passive"))
      (node (ref "C36") (pin "1") (pinfunction "1_1") (pintype "passive"))
      (node (ref "C37") (pin "1") (pinfunction "1_1") (pintype "passive"))
      (node (ref "C38") (pin "1") (pinfunction "1_1") (pintype "passive"))
      (node (ref "C39") (pin "2") (pinfunction "2_2") (pintype "passive"))
      (node (ref "C40") (pin "2") (pinfunction "2_2") (pintype "passive"))
      (node (ref "C41") (pin "2") (pinfunction "2_2") (pintype "passive"))
      (node (ref "C42") (pin "2") (pinfunction "2_2") (pintype "passive"))
      (node (ref "C43") (pin "2") (pinfunction "2_2") (pintype "passive"))
      (node (ref "C44") (pin "2") (pinfunction "2_2") (pintype "passive"))
      (node (ref "C45") (pin "2") (pinfunction "2_2") (pintype "passive"))
      (node (ref "C46") (pin "2") (pinfunction "2_2") (pintype "passive"))
      (node (ref "C47") (pin "2") (pinfunction "2_2") (pintype "passive"))
      (node (ref "C48") (pin "2") (pinfunction "2_2") (pintype "passive"))
      (node (ref "C49") (pin "2") (pinfunction "2_2") (pintype "passive"))
      (node (ref "C50") (pin "2") (pinfunction "2_2") (pintype "passive"))
      (node (ref "C51") (pin "2") (pinfunction "2_2") (pintype "passive"))
      (node (ref "C52") (pin "2") (pinfunction "2_2") (pintype "passive"))
      (node (ref "C53") (pin "2") (pinfunction "2_2") (pintype "passive"))
      (node (ref "C54") (pin "2") (pinfunction "2_2") (pintype "passive"))
      (node (ref "C55") (pin "2") (pinfunction "2_2") (pintype "passive"))
      (node (ref "C7") (pin "1") (pinfunction "1_1") (pintype "passive"))
      (node (ref "C8") (pin "1") (pinfunction "1_1") (pintype "passive"))
      (node (ref "D10") (pin "1") (pinfunction "A_1") (pintype "passive"))
      (node (ref "D11") (pin "1") (pinfunction "A_1") (pintype "passive"))
      (node (ref "D12") (pin "1") (pinfunction "A_1") (pintype "passive"))
      (node (ref "D13") (pin "1") (pinfunction "A_1") (pintype "passive"))
      (node (ref "D14") (pin "1") (pinfunction "A_1") (pintype "passive"))
      (node (ref "D15") (pin "1") (pinfunction "A_1") (pintype "passive"))
      (node (ref "D16") (pin "1") (pinfunction "A_1") (pintype "passive"))
      (node (ref "D17") (pin "1") (pinfunction "A_1") (pintype "passive"))
      (node (ref "D8") (pin "1") (pinfunction "A_1") (pintype "passive"))
      (node (ref "D9") (pin "1") (pinfunction "A_1") (pintype "passive"))
      (node (ref "J2") (pin "2") (pinfunction "Y_2") (pintype "passive"))
      (node (ref "J3") (pin "2") (pinfunction "2_2") (pintype "passive"))
      (node (ref "J3") (pin "5") (pinfunction "5_5") (pintype "passive"))
      (node (ref "J4") (pin "10") (pinfunction "Case_10") (pintype "passive"))
      (node (ref "J4") (pin "6") (pinfunction "GND_6") (pintype "power_in"))
      (node (ref "J5") (pin "8") (pinfunction "8_8") (pintype "passive"))
      (node (ref "Pp") (pin "3") (pinfunction "3_3") (pintype "passive"))
      (node (ref "Q1") (pin "2") (pinfunction "S_2") (pintype "passive"))
      (node (ref "Q2") (pin "2") (pinfunction "S_2") (pintype "passive"))
      (node (ref "Q3") (pin "2") (pinfunction "S_2") (pintype "passive"))
      (node (ref "Q8") (pin "2") (pinfunction "S_2") (pintype "passive"))
      (node (ref "R42") (pin "2") (pinfunction "2_2") (pintype "passive"))
      (node (ref "R45") (pin "2") (pinfunction "2_2") (pintype "passive"))
      (node (ref "R48") (pin "1") (pinfunction "1_1") (pintype "passive"))
      (node (ref "Sw1") (pin "1") (pintype "passive"))
      (node (ref "U1") (pin "1") (pinfunction "GND_1") (pintype "power_in"))
      (node (ref "U1") (pin "10") (pinfunction "GND_10") (pintype "power_in"))
      (node (ref "U1") (pin "12") (pinfunction "GND_12") (pintype "power_in"))
      (node (ref "U2") (pin "20") (pinfunction "AVSS_20") (pintype "power_in"))
      (node (ref "U2") (pin "25") (pinfunction "VSS_25") (pintype "power_in"))
      (node (ref "U2") (pin "41") (pinfunction "VSS_41") (pintype "power_in"))
      (node (ref "U2") (pin "9") (pinfunction "VSS_9") (pintype "power_in"))
      (node (ref "U3") (pin "2") (pinfunction "GND_2") (pintype "power_in"))
      (node (ref "U4") (pin "3") (pinfunction "GND_3") (pintype "power_in"))
    )
    (net (code "42") (name "Net-(B2-+)") (class "Default")
      (node (ref "B2") (pin "1") (pinfunction "+_1") (pintype "passive"))
      (node (ref "R6") (pin "1") (pinfunction "1_1") (pintype "passive"))
      (node (ref "U1") (pin "6") (pinfunction "Vbckp_6") (pintype "input"))
    )
    (net (code "43") (name "Net-(C18-Pad2)") (class "Default")
      (node (ref "C18") (pin "2") (pinfunction "2_2") (pintype "passive"))
      (node (ref "R12") (pin "1") (pinfunction "1_1") (pintype "passive"))
      (node (ref "R16") (pin "2") (pinfunction "2_2") (pintype "passive"))
    )
    (net (code "44") (name "Net-(C20-Pad2)") (class "Default")
      (node (ref "C20") (pin "2") (pinfunction "2_2") (pintype "passive"))
      (node (ref "R16") (pin "1") (pinfunction "1_1") (pintype "passive"))
      (node (ref "R48") (pin "2") (pinfunction "2_2") (pintype "passive"))
    )
    (net (code "45") (name "Net-(C28-Pad2)") (class "Default")
      (node (ref "C28") (pin "2") (pinfunction "2_2") (pintype "passive"))
      (node (ref "R34") (pin "1") (pinfunction "1_1") (pintype "passive"))
      (node (ref "R8") (pin "1") (pinfunction "1_1") (pintype "passive"))
    )
    (net (code "46") (name "Net-(C43-Pad1)") (class "Default")
      (node (ref "C43") (pin "1") (pinfunction "1_1") (pintype "passive"))
      (node (ref "J3") (pin "7") (pinfunction "7_7") (pintype "passive"))
      (node (ref "L6") (pin "2") (pinfunction "2_2") (pintype "passive"))
    )
    (net (code "47") (name "Net-(C44-Pad1)") (class "Default")
      (node (ref "C44") (pin "1") (pinfunction "1_1") (pintype "passive"))
      (node (ref "J3") (pin "6") (pinfunction "6_6") (pintype "passive"))
      (node (ref "L5") (pin "2") (pinfunction "2_2") (pintype "passive"))
    )
    (net (code "48") (name "Net-(C45-Pad1)") (class "Default")
      (node (ref "C45") (pin "1") (pinfunction "1_1") (pintype "passive"))
      (node (ref "J3") (pin "4") (pinfunction "4_4") (pintype "passive"))
      (node (ref "L4") (pin "2") (pinfunction "2_2") (pintype "passive"))
    )
    (net (code "49") (name "Net-(C46-Pad1)") (class "Default")
      (node (ref "C46") (pin "1") (pinfunction "1_1") (pintype "passive"))
      (node (ref "J3") (pin "3") (pinfunction "3_3") (pintype "passive"))
      (node (ref "L3") (pin "2") (pinfunction "2_2") (pintype "passive"))
    )
    (net (code "50") (name "Net-(C47-Pad1)") (class "Default")
      (node (ref "C47") (pin "1") (pinfunction "1_1") (pintype "passive"))
      (node (ref "J3") (pin "1") (pinfunction "1_1") (pintype "passive"))
      (node (ref "L2") (pin "2") (pinfunction "2_2") (pintype "passive"))
    )
    (net (code "51") (name "Net-(C48-Pad1)") (class "Default")
      (node (ref "C48") (pin "1") (pinfunction "1_1") (pintype "passive"))
      (node (ref "J3") (pin "8") (pinfunction "8_8") (pintype "passive"))
      (node (ref "L7") (pin "1") (pinfunction "1_1") (pintype "passive"))
    )
    (net (code "52") (name "Net-(D2-K)") (class "Default")
      (node (ref "D2") (pin "2") (pinfunction "K_2") (pintype "passive"))
      (node (ref "R8") (pin "2") (pinfunction "2_2") (pintype "passive"))
    )
    (net (code "53") (name "Net-(D6-A)") (class "Default")
      (node (ref "C17") (pin "2") (pinfunction "2_2") (pintype "passive"))
      (node (ref "D6") (pin "1") (pinfunction "A_1") (pintype "passive"))
      (node (ref "R13") (pin "1") (pinfunction "1_1") (pintype "passive"))
      (node (ref "R14") (pin "2") (pinfunction "2_2") (pintype "passive"))
    )
    (net (code "54") (name "Net-(D7-K)") (class "Default")
      (node (ref "D7") (pin "3") (pinfunction "K_3") (pintype "passive"))
      (node (ref "R6") (pin "2") (pinfunction "2_2") (pintype "passive"))
    )
    (net (code "55") (name "Net-(J2-X)") (class "Default")
      (node (ref "C29") (pin "1") (pinfunction "1_1") (pintype "passive"))
      (node (ref "J2") (pin "1") (pinfunction "X_1") (pintype "passive"))
      (node (ref "L1") (pin "2") (pinfunction "2_2") (pintype "passive"))
    )
    (net (code "56") (name "Net-(J4-Vdd)") (class "Default")
      (node (ref "C38") (pin "2") (pinfunction "2_2") (pintype "passive"))
      (node (ref "J4") (pin "4") (pinfunction "Vdd_4") (pintype "power_in"))
      (node (ref "R35") (pin "1") (pinfunction "1_1") (pintype "passive"))
      (node (ref "R36") (pin "1") (pinfunction "1_1") (pintype "passive"))
      (node (ref "R37") (pin "1") (pinfunction "1_1") (pintype "passive"))
      (node (ref "R38") (pin "1") (pinfunction "1_1") (pintype "passive"))
      (node (ref "R41") (pin "2") (pinfunction "2_2") (pintype "passive"))
      (node (ref "R46") (pin "2") (pinfunction "2_2") (pintype "passive"))
      (node (ref "U3") (pin "5") (pinfunction "Vout_5") (pintype "passive"))
    )
    (net (code "57") (name "Net-(J5-Pad1)") (class "Default")
      (node (ref "J5") (pin "1") (pinfunction "1_1") (pintype "passive"))
      (node (ref "L8") (pin "2") (pinfunction "2_2") (pintype "passive"))
    )
    (net (code "58") (name "Net-(J5-Pad2)") (class "Default")
      (node (ref "J5") (pin "2") (pinfunction "2_2") (pintype "passive"))
      (node (ref "L9") (pin "2") (pinfunction "2_2") (pintype "passive"))
    )
    (net (code "59") (name "Net-(J5-Pad3)") (class "Default")
      (node (ref "J5") (pin "3") (pinfunction "3_3") (pintype "passive"))
      (node (ref "L10") (pin "2") (pinfunction "2_2") (pintype "passive"))
    )
    (net (code "60") (name "Net-(J5-Pad4)") (class "Default")
      (node (ref "J5") (pin "4") (pinfunction "4_4") (pintype "passive"))
      (node (ref "L11") (pin "2") (pinfunction "2_2") (pintype "passive"))
    )
    (net (code "61") (name "Net-(J5-Pad5)") (class "Default")
      (node (ref "J5") (pin "5") (pinfunction "5_5") (pintype "passive"))
      (node (ref "L12") (pin "2") (pinfunction "2_2") (pintype "passive"))
    )
    (net (code "62") (name "Net-(J5-Pad6)") (class "Default")
      (node (ref "J5") (pin "6") (pinfunction "6_6") (pintype "passive"))
      (node (ref "L13") (pin "2") (pinfunction "2_2") (pintype "passive"))
    )
    (net (code "63") (name "Net-(J5-Pad7)") (class "Default")
      (node (ref "J5") (pin "7") (pinfunction "7_7") (pintype "passive"))
      (node (ref "L14") (pin "2") (pinfunction "2_2") (pintype "passive"))
    )
    (net (code "64") (name "Net-(LED1A-A)") (class "Default")
      (node (ref "LED1") (pin "2u") (pinfunction "A_2u") (pintype "passive"))
      (node (ref "R19") (pin "2") (pinfunction "2_2") (pintype "passive"))
    )
    (net (code "65") (name "Net-(LED1A-K)") (class "Default")
      (node (ref "LED1") (pin "1u") (pinfunction "K_1u") (pintype "passive"))
      (node (ref "LED1") (pin "3u") (pinfunction "K_3u") (pintype "passive"))
      (node (ref "Sw1") (pin "2") (pintype "passive"))
    )
    (net (code "66") (name "Net-(Q1-D)") (class "Default")
      (node (ref "C28") (pin "1") (pinfunction "1_1") (pintype "passive"))
      (node (ref "Q1") (pin "3") (pinfunction "D_3") (pintype "passive"))
      (node (ref "R34") (pin "2") (pinfunction "2_2") (pintype "passive"))
    )
    (net (code "67") (name "Net-(Q2-G)") (class "Default")
      (node (ref "Q2") (pin "1") (pinfunction "G_1") (pintype "passive"))
      (node (ref "R49") (pin "1") (pinfunction "1_1") (pintype "passive"))
    )
    (net (code "68") (name "Net-(Q8-D)") (class "Default")
      (node (ref "Q8") (pin "3") (pinfunction "D_3") (pintype "passive"))
      (node (ref "Q9") (pin "1") (pinfunction "G_1") (pintype "passive"))
      (node (ref "R33") (pin "2") (pinfunction "2_2") (pintype "passive"))
    )
    (net (code "69") (name "Net-(Q9-D)") (class "Default")
      (node (ref "C30") (pin "1") (pinfunction "1_1") (pintype "passive"))
      (node (ref "L1") (pin "1") (pinfunction "1_1") (pintype "passive"))
      (node (ref "Q9") (pin "3") (pinfunction "D_3") (pintype "passive"))
      (node (ref "R39") (pin "2") (pinfunction "2_2") (pintype "passive"))
    )
    (net (code "70") (name "Net-(Q9-S)") (class "Default")
      (node (ref "C27") (pin "2") (pinfunction "2_2") (pintype "passive"))
      (node (ref "FB1") (pin "2") (pinfunction "2_2") (pintype "passive"))
      (node (ref "Q9") (pin "2") (pinfunction "S_2") (pintype "passive"))
      (node (ref "R39") (pin "1") (pinfunction "1_1") (pintype "passive"))
    )
    (net (code "71") (name "Net-(U1-RF_in)") (class "Default")
      (node (ref "C29") (pin "2") (pinfunction "2_2") (pintype "passive"))
      (node (ref "U1") (pin "11") (pinfunction "RF_in_11") (pintype "input"))
    )
    (net (code "72") (name "Net-(U1-~{Reset})") (class "Default")
      (node (ref "C8") (pin "2") (pinfunction "2_2") (pintype "passive"))
      (node (ref "R5") (pin "1") (pinfunction "1_1") (pintype "passive"))
      (node (ref "U1") (pin "9") (pinfunction "~{Reset}_9") (pintype "input"))
    )
    (net (code "73") (name "Net-(U2-VCAP{slash}VDDCORE)") (class "Default")
      (node (ref "C36") (pin "2") (pinfunction "2_2") (pintype "passive"))
      (node (ref "U2") (pin "56") (pinfunction "VCAP/VDDCORE_56") (pintype "power_in"))
    )
    (net (code "74") (name "unconnected-(J4-DAT1{slash}Reserved-Pad8)") (class "Default")
      (node (ref "J4") (pin "8") (pinfunction "DAT1/Reserved_8") (pintype "passive"))
    )
    (net (code "75") (name "unconnected-(J4-DAT2{slash}Reserved-Pad1)") (class "Default")
      (node (ref "J4") (pin "1") (pinfunction "DAT2/Reserved_1") (pintype "passive"))
    )
    (net (code "76") (name "unconnected-(Pp-Pad6)") (class "Default")
      (node (ref "Pp") (pin "6") (pinfunction "6_6") (pintype "passive"))
    )
    (net (code "77") (name "unconnected-(Sw1-Pad3)") (class "Default")
      (node (ref "Sw1") (pin "3") (pintype "passive"))
    )
    (net (code "78") (name "unconnected-(U1-ExtINT-Pad5)") (class "Default")
      (node (ref "U1") (pin "5") (pinfunction "ExtINT_5") (pintype "input+no_connect"))
    )
    (net (code "79") (name "unconnected-(U1-NC-Pad7)") (class "Default")
      (node (ref "U1") (pin "7") (pinfunction "NC_7") (pintype "passive+no_connect"))
    )
    (net (code "80") (name "unconnected-(U1-NC-Pad15)") (class "Default")
      (node (ref "U1") (pin "15") (pinfunction "NC_15") (pintype "passive+no_connect"))
    )
    (net (code "81") (name "unconnected-(U1-NC-Pad16)") (class "Default")
      (node (ref "U1") (pin "16") (pinfunction "NC_16") (pintype "passive+no_connect"))
    )
    (net (code "82") (name "unconnected-(U1-NC-Pad17)") (class "Default")
      (node (ref "U1") (pin "17") (pinfunction "NC_17") (pintype "passive+no_connect"))
    )
    (net (code "83") (name "unconnected-(U1-NC-Pad18)") (class "Default")
      (node (ref "U1") (pin "18") (pinfunction "NC_18") (pintype "passive+no_connect"))
    )
    (net (code "84") (name "unconnected-(U1-VccRF-Pad14)") (class "Default")
      (node (ref "U1") (pin "14") (pinfunction "VccRF_14") (pintype "output"))
    )
    (net (code "85") (name "unconnected-(U2-AN2{slash}C2INB{slash}RP13{slash}CN4{slash}RB2-Pad14)") (class "Default")
      (node (ref "U2") (pin "14") (pinfunction "AN2/C2INB/RP13/CN4/RB2_14") (pintype "bidirectional"))
    )
    (net (code "86") (name "unconnected-(U2-AN3{slash}C2INA{slash}CN5{slash}RB3-Pad13)") (class "Default")
      (node (ref "U2") (pin "13") (pinfunction "AN3/C2INA/CN5/RB3_13") (pintype "bidirectional"))
    )
    (net (code "87") (name "unconnected-(U2-ASCK1{slash}RPI45{slash}INT0{slash}CN72{slash}RF6-Pad35)") (class "Default")
      (node (ref "U2") (pin "35") (pinfunction "ASCK1/RPI45/INT0/CN72/RF6_35") (pintype "bidirectional"))
    )
    (net (code "88") (name "unconnected-(U2-CN58{slash}PMD0{slash}RE0-Pad60)") (class "Default")
      (node (ref "U2") (pin "60") (pinfunction "CN58/PMD0/RE0_60") (pintype "bidirectional"))
    )
    (net (code "89") (name "unconnected-(U2-CN60{slash}PMD2{slash}RE2-Pad62)") (class "Default")
      (node (ref "U2") (pin "62") (pinfunction "CN60/PMD2/RE2_62") (pintype "bidirectional"))
    )
    (net (code "90") (name "unconnected-(U2-CN61{slash}PMD3{slash}RE3-Pad63)") (class "Default")
      (node (ref "U2") (pin "63") (pinfunction "CN61/PMD3/RE3_63") (pintype "bidirectional"))
    )
    (net (code "91") (name "unconnected-(U2-CN62{slash}PMD4{slash}RE4-Pad64)") (class "Default")
      (node (ref "U2") (pin "64") (pinfunction "CN62/PMD4/RE4_64") (pintype "bidirectional"))
    )
    (net (code "92") (name "unconnected-(U2-CN63{slash}PMD5{slash}RE5-Pad1)") (class "Default")
      (node (ref "U2") (pin "1") (pinfunction "CN63/PMD5/RE5_1") (pintype "bidirectional"))
    )
    (net (code "93") (name "unconnected-(U2-ENVREG-Pad57)") (class "Default")
      (node (ref "U2") (pin "57") (pinfunction "ENVREG_57") (pintype "input"))
    )
    (net (code "94") (name "unconnected-(U2-OSCI{slash}CLKI{slash}CN23{slash}RC12-Pad39)") (class "Default")
      (node (ref "U2") (pin "39") (pinfunction "OSCI/CLKI/CN23/RC12_39") (pintype "bidirectional"))
    )
    (net (code "95") (name "unconnected-(U2-OSCO{slash}CLKO{slash}CN22{slash}RC15-Pad40)") (class "Default")
      (node (ref "U2") (pin "40") (pinfunction "OSCO/CLKO/CN22/RC15_40") (pintype "bidirectional"))
    )
    (net (code "96") (name "unconnected-(U2-PGEC2{slash}AN6{slash}RP6{slash}CN24{slash}RB6-Pad17)") (class "Default")
      (node (ref "U2") (pin "17") (pinfunction "PGEC2/AN6/RP6/CN24/RB6_17") (pintype "bidirectional"))
    )
    (net (code "97") (name "unconnected-(U2-PGEC3{slash}AN5{slash}C1INA{slash}RP18{slash}CN7{slash}RB5-Pad11)") (class "Default")
      (node (ref "U2") (pin "11") (pinfunction "PGEC3/AN5/C1INA/RP18/CN7/RB5_11") (pintype "bidirectional"))
    )
    (net (code "98") (name "unconnected-(U2-PGED2{slash}AN7{slash}RP7{slash}CN25{slash}RB7-Pad18)") (class "Default")
      (node (ref "U2") (pin "18") (pinfunction "PGED2/AN7/RP7/CN25/RB7_18") (pintype "bidirectional"))
    )
    (net (code "99") (name "unconnected-(U2-RP16{slash}CN71{slash}RF3-Pad33)") (class "Default")
      (node (ref "U2") (pin "33") (pinfunction "RP16/CN71/RF3_33") (pintype "bidirectional"))
    )
    (net (code "100") (name "unconnected-(U2-RP22{slash}CN52{slash}PMBE{slash}RD3-Pad51)") (class "Default")
      (node (ref "U2") (pin "51") (pinfunction "RP22/CN52/PMBE/RD3_51") (pintype "bidirectional"))
    )
    (net (code "101") (name "unconnected-(U2-RP30{slash}CN70{slash}RF2-Pad34)") (class "Default")
      (node (ref "U2") (pin "34") (pinfunction "RP30/CN70/RF2_34") (pintype "bidirectional"))
    )
    (net (code "102") (name "unconnected-(U2-SCL1{slash}CN83{slash}RG2-Pad37)") (class "Default")
      (node (ref "U2") (pin "37") (pinfunction "SCL1/CN83/RG2_37") (pintype "bidirectional"))
    )
    (net (code "103") (name "unconnected-(U2-SCL3{slash}CN64{slash}PMD6{slash}RE6-Pad2)") (class "Default")
      (node (ref "U2") (pin "2") (pinfunction "SCL3/CN64/PMD6/RE6_2") (pintype "bidirectional"))
    )
    (net (code "104") (name "unconnected-(U2-SDA1{slash}CN84{slash}RG3-Pad36)") (class "Default")
      (node (ref "U2") (pin "36") (pinfunction "SDA1/CN84/RG3_36") (pintype "bidirectional"))
    )
    (net (code "105") (name "unconnected-(U2-SOSCI{slash}C3IND{slash}CN1{slash}RC13-Pad47)") (class "Default")
      (node (ref "U2") (pin "47") (pinfunction "SOSCI/C3IND/CN1/RC13_47") (pintype "bidirectional"))
    )
    (net (code "106") (name "unconnected-(U2-SOSCO{slash}C3INC{slash}RPI37{slash}CN0{slash}RC14-Pad48)") (class "Default")
      (node (ref "U2") (pin "48") (pinfunction "SOSCO/C3INC/RPI37/CN0/RC14_48") (pintype "bidirectional"))
    )
    (net (code "107") (name "unconnected-(U2-TCK{slash}AN12{slash}CTED2{slash}CN30{slash}PMA11{slash}RB12-Pad27)") (class "Default")
      (node (ref "U2") (pin "27") (pinfunction "TCK/AN12/CTED2/CN30/PMA11/RB12_27") (pintype "bidirectional"))
    )
    (net (code "108") (name "unconnected-(U2-TDO{slash}AN11{slash}CN29{slash}PMA12{slash}RB11-Pad24)") (class "Default")
      (node (ref "U2") (pin "24") (pinfunction "TDO/AN11/CN29/PMA12/RB11_24") (pintype "bidirectional"))
    )
    (net (code "109") (name "unconnected-(U2-TMS{slash}AN10{slash}CVREF{slash}CN28{slash}PMA13{slash}RB10-Pad23)") (class "Default")
      (node (ref "U2") (pin "23") (pinfunction "TMS/AN10/CVREF/CN28/PMA13/RB10_23") (pintype "bidirectional"))
    )
  )
)
